# 01_Power.net
KiCad netlist of a schematic drawn in Altium Designer
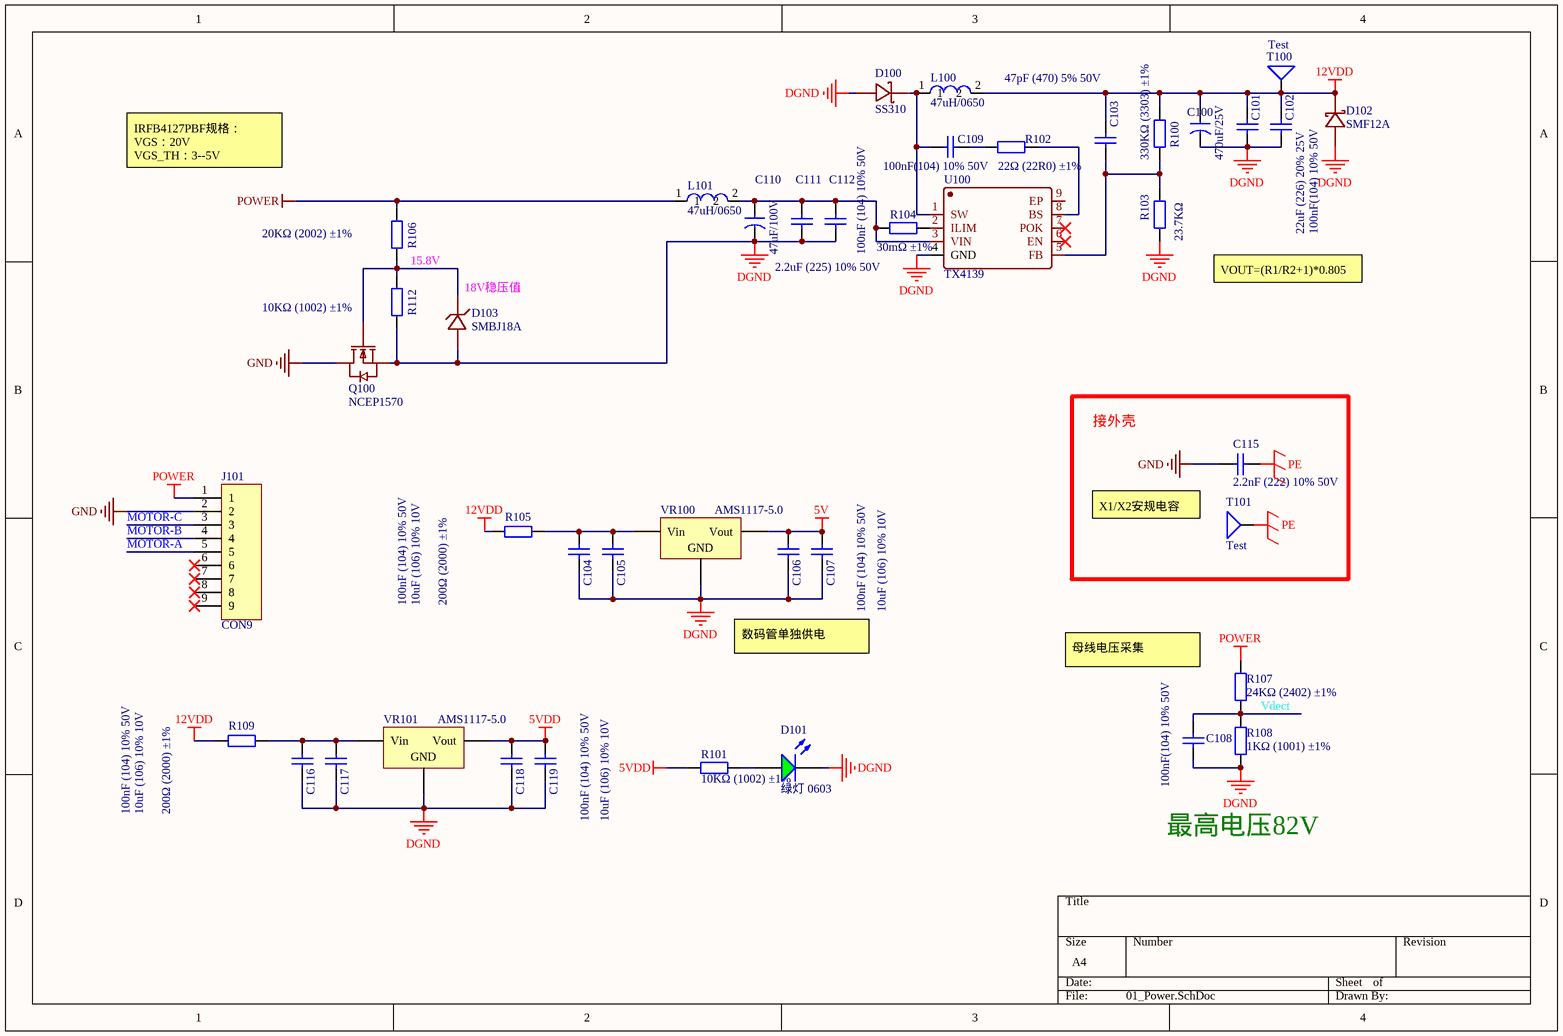
[diagram p0: 01_Power.SchDoc]

(export (version "E")
  (design (tool "Eeschema 10.0.6"))
  (components
    (comp (ref "C100")
      (value "470uF/25V")
      (footprint "47UF/100V")
      (libsource (lib "RayPCB20210502") (part "CapSMT220u_16V"))
    )
    (comp (ref "C101")
      (value "22uF (226) 20% 25V")
      (footprint "0805_C")
      (description "贴片电容")
      (libsource (lib "Miscellaneous Devices LC") (part "0805 22uF (226) 20% 25V"))
    )
    (comp (ref "C102")
      (value "100nF(104) 10% 50V")
      (footprint "0805_C")
      (description "贴片电容")
      (libsource (lib "Miscellaneous Devices LC") (part "0805 100nF(104) 10% 50V"))
    )
    (comp (ref "C103")
      (value "47pF (470) 5% 50V")
      (footprint "0805_C")
      (description "贴片电容")
      (libsource (lib "Miscellaneous Devices LC") (part "0805 47pF (470) 5% 50V"))
    )
    (comp (ref "C104")
      (value "100nF (104) 10% 50V")
      (footprint "0603_C")
      (description "贴片电容")
      (libsource (lib "Miscellaneous Devices LC") (part "0603 100nF (104) 10% 50V"))
    )
    (comp (ref "C105")
      (value "10uF (106) 10% 10V")
      (footprint "0603_C")
      (description "贴片电容")
      (libsource (lib "Miscellaneous Devices LC") (part "0603 10uF (106) 10% 10V"))
    )
    (comp (ref "C106")
      (value "100nF (104) 10% 50V")
      (footprint "0603_C")
      (description "贴片电容")
      (libsource (lib "Miscellaneous Devices LC") (part "0603 100nF (104) 10% 50V"))
    )
    (comp (ref "C107")
      (value "10uF (106) 10% 10V")
      (footprint "0603_C")
      (description "贴片电容")
      (libsource (lib "Miscellaneous Devices LC") (part "0603 10uF (106) 10% 10V"))
    )
    (comp (ref "C108")
      (value "100nF(104) 10% 50V")
      (footprint "0805_C")
      (description "贴片电容")
      (libsource (lib "Miscellaneous Devices LC") (part "0805 100nF(104) 10% 50V"))
    )
    (comp (ref "C109")
      (value "100nF(104) 10% 50V")
      (footprint "0805_C")
      (description "贴片电容")
      (libsource (lib "Miscellaneous Devices LC") (part "0805 100nF(104) 10% 50V"))
    )
    (comp (ref "C110")
      (value "47uF/100V")
      (footprint "47UF/100V")
      (libsource (lib "RayPCB20210502") (part "CapSMT220u_16V"))
    )
    (comp (ref "C111")
      (value "2.2uF (225) 10% 50V")
      (footprint "1206_C")
      (description "贴片电容")
      (libsource (lib "Miscellaneous Devices LC") (part "1206 2.2uF (225) 10% 50V"))
    )
    (comp (ref "C112")
      (value "100nF (104) 10% 50V")
      (footprint "1206_C")
      (description "贴片电容")
      (libsource (lib "Miscellaneous Devices LC") (part "1206 100nF (104) 10% 50V"))
    )
    (comp (ref "C115")
      (value "2.2nF (222) 10% 50V")
      (footprint "X1/Y1 500V")
      (description "贴片电容")
      (libsource (lib "Miscellaneous Devices LC") (part "0603 2.2nF (222) 10% 50V"))
    )
    (comp (ref "C116")
      (value "100nF (104) 10% 50V")
      (footprint "0603_C")
      (description "贴片电容")
      (libsource (lib "Miscellaneous Devices LC") (part "0603 100nF (104) 10% 50V"))
    )
    (comp (ref "C117")
      (value "10uF (106) 10% 10V")
      (footprint "0603_C")
      (description "贴片电容")
      (libsource (lib "Miscellaneous Devices LC") (part "0603 10uF (106) 10% 10V"))
    )
    (comp (ref "C118")
      (value "100nF (104) 10% 50V")
      (footprint "0603_C")
      (description "贴片电容")
      (libsource (lib "Miscellaneous Devices LC") (part "0603 100nF (104) 10% 50V"))
    )
    (comp (ref "C119")
      (value "10uF (106) 10% 10V")
      (footprint "0603_C")
      (description "贴片电容")
      (libsource (lib "Miscellaneous Devices LC") (part "0603 10uF (106) 10% 10V"))
    )
    (comp (ref "D100") (value "SS310") (footprint "SS310") (libsource (lib "Schlibv2") (part "SS310")))
    (comp (ref "D101")
      (value "绿灯 0603")
      (footprint "0603_LED_S1")
      (description "发光二极管")
      (libsource (lib "Miscellaneous Devices LC") (part "0603 绿灯"))
    )
    (comp (ref "D102")
      (value "SMF12A")
      (footprint "SMF12A - duplicate")
      (libsource (lib "RayPCB20210502") (part "SMF12A"))
    )
    (comp (ref "D103") (value "SMBJ18A") (footprint "SMBJ18A") (libsource (lib "Schlibv2") (part "1N4746A")))
    (comp (ref "J101")
      (value "CON9")
      (footprint "CON9 9.5mm")
      (libsource (lib "RayPCB20210502") (part "CON9"))
    )
    (comp (ref "L100")
      (value "47uH/0650")
      (footprint "0650_47uH")
      (libsource (lib "RayPCB20210502") (part "Inductor"))
    )
    (comp (ref "L101")
      (value "47uH/0650")
      (footprint "0650_47uH")
      (libsource (lib "RayPCB20210502") (part "Inductor"))
    )
    (comp (ref "Q100")
      (value "NCEP1570")
      (footprint "NCEP1570")
      (libsource (lib "RayPCB20210502") (part "IRFB4127PBF"))
    )
    (comp (ref "R100")
      (value "330KΩ (3303) ±1%")
      (footprint "0805_R")
      (description "贴片电阻")
      (libsource (lib "Miscellaneous Devices LC") (part "0805 330KΩ (3303) 1%"))
    )
    (comp (ref "R101")
      (value "10KΩ (1002) ±1%")
      (footprint "0603_R")
      (description "贴片电阻")
      (libsource (lib "Miscellaneous Devices LC") (part "0603 10KΩ (1002) 1%"))
    )
    (comp (ref "R102")
      (value "22Ω (22R0) ±1%")
      (footprint "0805_R")
      (description "贴片电阻")
      (libsource (lib "Miscellaneous Devices LC") (part "0805 22Ω (22R0) 1%"))
    )
    (comp (ref "R103")
      (value "23.7KΩ")
      (footprint "0805_R")
      (description "贴片电阻")
      (libsource (lib "") (part "0805 22Ω (22R0) 1%_1"))
    )
    (comp (ref "R104")
      (value "30mΩ ±1%")
      (footprint "0603_R")
      (description "贴片电阻")
      (libsource (lib "Miscellaneous Devices LC") (part "0603 100KΩ (1003) 1%"))
    )
    (comp (ref "R105")
      (value "200Ω (2000) ±1%")
      (footprint "1206_R")
      (description "贴片电阻")
      (libsource (lib "Miscellaneous Devices LC") (part "1206 300Ω (3000) 1%"))
    )
    (comp (ref "R106")
      (value "20KΩ (2002) ±1%")
      (footprint "0805_R")
      (description "贴片电阻")
      (libsource (lib "Miscellaneous Devices LC") (part "0805 20KΩ (2002) 1%"))
    )
    (comp (ref "R107")
      (value "24KΩ (2402) ±1%")
      (footprint "1206_R")
      (description "贴片电阻")
      (libsource (lib "Miscellaneous Devices LC") (part "1206 0Ω (0R0) 1%"))
    )
    (comp (ref "R108")
      (value "1KΩ (1001) ±1%")
      (footprint "0805_R")
      (description "贴片电阻")
      (libsource (lib "Miscellaneous Devices LC") (part "0805 1KΩ (1001) 1%"))
    )
    (comp (ref "R109")
      (value "200Ω (2000) ±1%")
      (footprint "1206_R")
      (description "贴片电阻")
      (libsource (lib "Miscellaneous Devices LC") (part "1206 300Ω (3000) 1%"))
    )
    (comp (ref "R112")
      (value "10KΩ (1002) ±1%")
      (footprint "0805_R")
      (description "贴片电阻")
      (libsource (lib "Miscellaneous Devices LC") (part "0805 10KΩ (1002) 1%"))
    )
    (comp (ref "T100")
      (value "Test")
      (footprint "Testpoint")
      (libsource (lib "RayPCB20210502") (part "TestPad"))
    )
    (comp (ref "T101") (value "Test") (footprint "接地螺丝孔") (libsource (lib "RayPCB20210502") (part "TestPad")))
    (comp (ref "U100")
      (value "TX4139")
      (footprint "ESOP8")
      (libsource (lib "RayPCB20210502") (part "TX4139"))
    )
    (comp (ref "VR100")
      (value "AMS1117-5.0")
      (footprint "SOT-223")
      (description "低压差线性稳压(LDO)")
      (libsource (lib "Miscellaneous Devices LC") (part "SOT-223 AMS1117-5.0"))
    )
    (comp (ref "VR101")
      (value "AMS1117-5.0")
      (footprint "SOT-223")
      (description "低压差线性稳压(LDO)")
      (libsource (lib "Miscellaneous Devices LC") (part "SOT-223 AMS1117-5.0"))
    )
  )
  (nets
    (net (code "1") (name "/MOTOR-A") (class "Default")
      (node (ref "J101") (pin "5") (pinfunction "5_5") (pintype "passive"))
    )
    (net (code "2") (name "/MOTOR-B") (class "Default")
      (node (ref "J101") (pin "4") (pinfunction "4_4") (pintype "passive"))
    )
    (net (code "3") (name "/MOTOR-C") (class "Default")
      (node (ref "J101") (pin "3") (pinfunction "3_3") (pintype "passive"))
    )
    (net (code "4") (name "/Vdect") (class "Default")
      (node (ref "C108") (pin "2") (pinfunction "2_2") (pintype "passive"))
      (node (ref "R107") (pin "1") (pinfunction "1_1") (pintype "passive"))
      (node (ref "R108") (pin "2") (pinfunction "2_2") (pintype "passive"))
    )
    (net (code "5") (name "5V") (class "Default")
      (node (ref "C106") (pin "2") (pinfunction "2_2") (pintype "passive"))
      (node (ref "C107") (pin "2") (pinfunction "2_2") (pintype "passive"))
      (node (ref "VR100") (pin "2") (pinfunction "Vout_2") (pintype "passive"))
    )
    (net (code "6") (name "5VDD") (class "Default")
      (node (ref "C118") (pin "2") (pinfunction "2_2") (pintype "passive"))
      (node (ref "C119") (pin "2") (pinfunction "2_2") (pintype "passive"))
      (node (ref "R101") (pin "2") (pinfunction "2_2") (pintype "passive"))
      (node (ref "VR101") (pin "2") (pinfunction "Vout_2") (pintype "passive"))
    )
    (net (code "7") (name "12VDD") (class "Default")
      (node (ref "C100") (pin "1") (pintype "passive"))
      (node (ref "C101") (pin "2") (pinfunction "2_2") (pintype "passive"))
      (node (ref "C102") (pin "2") (pinfunction "2_2") (pintype "passive"))
      (node (ref "C103") (pin "2") (pinfunction "2_2") (pintype "passive"))
      (node (ref "D102") (pin "1") (pinfunction "K_1") (pintype "passive"))
      (node (ref "L100") (pin "2") (pinfunction "2_2") (pintype "passive"))
      (node (ref "R100") (pin "2") (pinfunction "2_2") (pintype "passive"))
      (node (ref "R105") (pin "1") (pinfunction "1_1") (pintype "passive"))
      (node (ref "R109") (pin "1") (pinfunction "1_1") (pintype "passive"))
      (node (ref "T100") (pin "1") (pinfunction "1_1") (pintype "passive"))
    )
    (net (code "8") (name "DGND") (class "Default")
      (node (ref "C100") (pin "2") (pintype "passive"))
      (node (ref "C101") (pin "1") (pinfunction "1_1") (pintype "passive"))
      (node (ref "C102") (pin "1") (pinfunction "1_1") (pintype "passive"))
      (node (ref "C104") (pin "1") (pinfunction "1_1") (pintype "passive"))
      (node (ref "C105") (pin "1") (pinfunction "1_1") (pintype "passive"))
      (node (ref "C106") (pin "1") (pinfunction "1_1") (pintype "passive"))
      (node (ref "C107") (pin "1") (pinfunction "1_1") (pintype "passive"))
      (node (ref "C108") (pin "1") (pinfunction "1_1") (pintype "passive"))
      (node (ref "C110") (pin "2") (pintype "passive"))
      (node (ref "C111") (pin "1") (pinfunction "1_1") (pintype "passive"))
      (node (ref "C112") (pin "1") (pinfunction "1_1") (pintype "passive"))
      (node (ref "C116") (pin "1") (pinfunction "1_1") (pintype "passive"))
      (node (ref "C117") (pin "1") (pinfunction "1_1") (pintype "passive"))
      (node (ref "C118") (pin "1") (pinfunction "1_1") (pintype "passive"))
      (node (ref "C119") (pin "1") (pinfunction "1_1") (pintype "passive"))
      (node (ref "D100") (pin "2") (pinfunction "A_2") (pintype "passive"))
      (node (ref "D101") (pin "K") (pinfunction "K_K") (pintype "passive"))
      (node (ref "D102") (pin "2") (pinfunction "A_2") (pintype "passive"))
      (node (ref "D103") (pin "1") (pinfunction "A_1") (pintype "passive"))
      (node (ref "Q100") (pin "3") (pinfunction "S_3") (pintype "passive"))
      (node (ref "R103") (pin "1") (pinfunction "1_1") (pintype "passive"))
      (node (ref "R108") (pin "1") (pinfunction "1_1") (pintype "passive"))
      (node (ref "R112") (pin "1") (pinfunction "1_1") (pintype "passive"))
      (node (ref "U100") (pin "4") (pinfunction "GND_4") (pintype "passive"))
      (node (ref "VR100") (pin "1") (pinfunction "GND_1") (pintype "passive"))
      (node (ref "VR101") (pin "1") (pinfunction "GND_1") (pintype "passive"))
    )
    (net (code "9") (name "GND") (class "Default")
      (node (ref "C115") (pin "1") (pinfunction "1_1") (pintype "passive"))
      (node (ref "J101") (pin "2") (pinfunction "2_2") (pintype "passive"))
      (node (ref "Q100") (pin "2") (pinfunction "D_2") (pintype "passive"))
    )
    (net (code "10") (name "Net-(C109-Pad2)") (class "Default")
      (node (ref "C109") (pin "2") (pinfunction "2_2") (pintype "passive"))
      (node (ref "R102") (pin "1") (pinfunction "1_1") (pintype "passive"))
    )
    (net (code "11") (name "Net-(D100-K)") (class "Default")
      (node (ref "C109") (pin "1") (pinfunction "1_1") (pintype "passive"))
      (node (ref "D100") (pin "1") (pinfunction "K_1") (pintype "passive"))
      (node (ref "L100") (pin "1") (pinfunction "1_1") (pintype "passive"))
      (node (ref "U100") (pin "1") (pinfunction "SW_1") (pintype "passive"))
    )
    (net (code "12") (name "Net-(D101-PadA)") (class "Default")
      (node (ref "D101") (pin "A") (pinfunction "A_A") (pintype "passive"))
      (node (ref "R101") (pin "1") (pinfunction "1_1") (pintype "passive"))
    )
    (net (code "13") (name "Net-(D103-K)") (class "Default")
      (node (ref "D103") (pin "2") (pinfunction "K_2") (pintype "passive"))
      (node (ref "Q100") (pin "1") (pinfunction "G_1") (pintype "passive"))
      (node (ref "R106") (pin "1") (pinfunction "1_1") (pintype "passive"))
      (node (ref "R112") (pin "2") (pinfunction "2_2") (pintype "passive"))
    )
    (net (code "14") (name "Net-(U100-BS)") (class "Default")
      (node (ref "R102") (pin "2") (pinfunction "2_2") (pintype "passive"))
      (node (ref "U100") (pin "8") (pinfunction "BS_8") (pintype "passive"))
    )
    (net (code "15") (name "Net-(U100-FB)") (class "Default")
      (node (ref "C103") (pin "1") (pinfunction "1_1") (pintype "passive"))
      (node (ref "R100") (pin "1") (pinfunction "1_1") (pintype "passive"))
      (node (ref "R103") (pin "2") (pinfunction "2_2") (pintype "passive"))
      (node (ref "U100") (pin "5") (pinfunction "FB_5") (pintype "passive"))
    )
    (net (code "16") (name "Net-(U100-ILIM)") (class "Default")
      (node (ref "R104") (pin "1") (pinfunction "1_1") (pintype "passive"))
      (node (ref "U100") (pin "2") (pinfunction "ILIM_2") (pintype "passive"))
    )
    (net (code "17") (name "Net-(U100-VIN)") (class "Default")
      (node (ref "C110") (pin "1") (pintype "passive"))
      (node (ref "C111") (pin "2") (pinfunction "2_2") (pintype "passive"))
      (node (ref "C112") (pin "2") (pinfunction "2_2") (pintype "passive"))
      (node (ref "L101") (pin "2") (pinfunction "2_2") (pintype "passive"))
      (node (ref "R104") (pin "2") (pinfunction "2_2") (pintype "passive"))
      (node (ref "U100") (pin "3") (pinfunction "VIN_3") (pintype "passive"))
    )
    (net (code "18") (name "Net-(VR100-Vin)") (class "Default")
      (node (ref "C104") (pin "2") (pinfunction "2_2") (pintype "passive"))
      (node (ref "C105") (pin "2") (pinfunction "2_2") (pintype "passive"))
      (node (ref "R105") (pin "2") (pinfunction "2_2") (pintype "passive"))
      (node (ref "VR100") (pin "3") (pinfunction "Vin_3") (pintype "passive"))
    )
    (net (code "19") (name "Net-(VR101-Vin)") (class "Default")
      (node (ref "C116") (pin "2") (pinfunction "2_2") (pintype "passive"))
      (node (ref "C117") (pin "2") (pinfunction "2_2") (pintype "passive"))
      (node (ref "R109") (pin "2") (pinfunction "2_2") (pintype "passive"))
      (node (ref "VR101") (pin "3") (pinfunction "Vin_3") (pintype "passive"))
    )
    (net (code "20") (name "PE") (class "Default")
      (node (ref "C115") (pin "2") (pinfunction "2_2") (pintype "passive"))
      (node (ref "T101") (pin "1") (pinfunction "1_1") (pintype "passive"))
    )
    (net (code "21") (name "POWER") (class "Default")
      (node (ref "J101") (pin "1") (pinfunction "1_1") (pintype "passive"))
      (node (ref "L101") (pin "1") (pinfunction "1_1") (pintype "passive"))
      (node (ref "R106") (pin "2") (pinfunction "2_2") (pintype "passive"))
      (node (ref "R107") (pin "2") (pinfunction "2_2") (pintype "passive"))
    )
    (net (code "22") (name "unconnected-(J101-Pad6)") (class "Default")
      (node (ref "J101") (pin "6") (pinfunction "6_6") (pintype "passive+no_connect"))
    )
    (net (code "23") (name "unconnected-(J101-Pad7)") (class "Default")
      (node (ref "J101") (pin "7") (pinfunction "7_7") (pintype "passive+no_connect"))
    )
    (net (code "24") (name "unconnected-(J101-Pad8)") (class "Default")
      (node (ref "J101") (pin "8") (pinfunction "8_8") (pintype "passive+no_connect"))
    )
    (net (code "25") (name "unconnected-(J101-Pad9)") (class "Default")
      (node (ref "J101") (pin "9") (pinfunction "9_9") (pintype "passive+no_connect"))
    )
    (net (code "26") (name "unconnected-(U100-EN-Pad6)") (class "Default")
      (node (ref "U100") (pin "6") (pinfunction "EN_6") (pintype "passive+no_connect"))
    )
    (net (code "27") (name "unconnected-(U100-EP-Pad9)") (class "Default")
      (node (ref "U100") (pin "9") (pinfunction "EP_9") (pintype "passive"))
    )
    (net (code "28") (name "unconnected-(U100-POK-Pad7)") (class "Default")
      (node (ref "U100") (pin "7") (pinfunction "POK_7") (pintype "passive+no_connect"))
    )
  )
)
